# CPU.net
KiCad netlist of a schematic drawn in Altium Designer
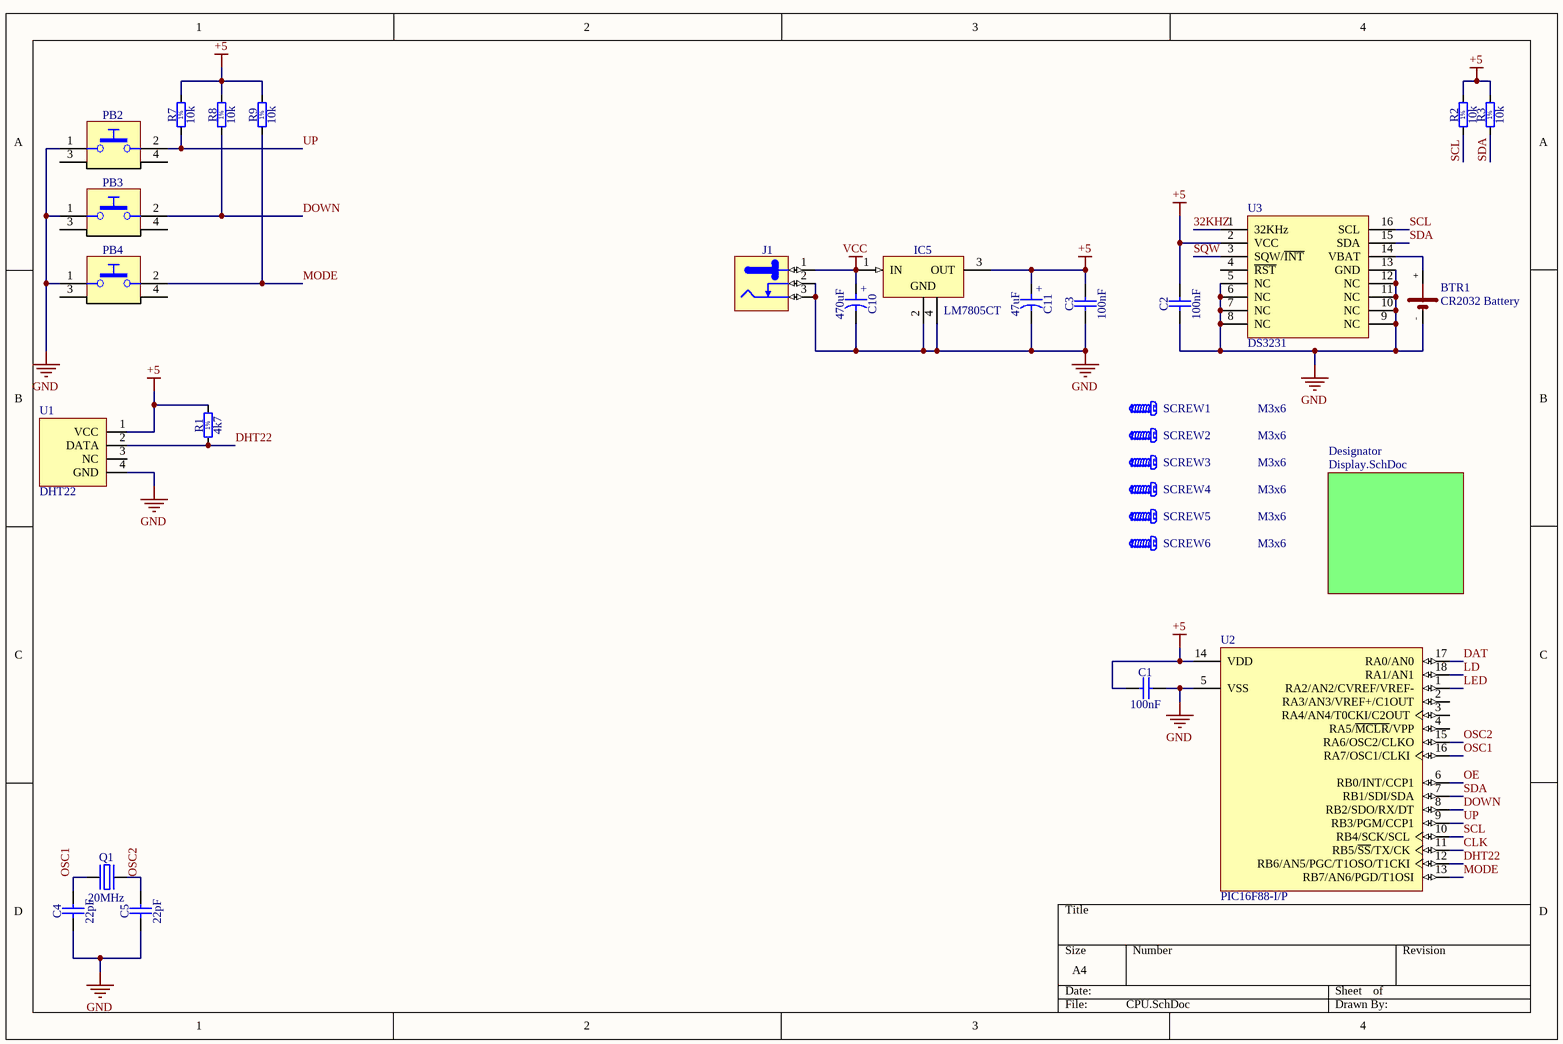
[diagram p0: CPU.SchDoc]

(export (version "E")
  (design (tool "Eeschema 10.0.6"))
  (components
    (comp (ref "BTR1")
      (value "CR2032 Battery")
      (footprint "cr1220")
      (libsource (lib "Shematic") (part "CR2032"))
    )
    (comp (ref "C1")
      (value "100nF")
      (footprint "CAPRR508-350X500X500")
      (description "Non-polarised capacitor")
      (fields
        (field (name "PART NUMBER") "CCR_100NF_50V_10%_X7R_508-350X500X500")
        (field (name "VOLTAGE") "50VDC")
        (field (name "AUTHOR") "CERN DEM JLC")
      )
      (libsource (lib "Capacitors") (part "Capacitor - non polarized"))
    )
    (comp (ref "C2")
      (value "100nF")
      (footprint "CAPRR508-350X500X500")
      (description "Non-polarised capacitor")
      (fields
        (field (name "PART NUMBER") "CCR_100NF_50V_10%_X7R_508-350X500X500")
        (field (name "VOLTAGE") "50VDC")
        (field (name "AUTHOR") "CERN DEM JLC")
      )
      (libsource (lib "Capacitors") (part "Capacitor - non polarized"))
    )
    (comp (ref "C3")
      (value "100nF")
      (footprint "CAPRR508-350X500X500")
      (description "Non-polarised capacitor")
      (fields
        (field (name "PART NUMBER") "CCR_100NF_50V_10%_X7R_508-350X500X500")
        (field (name "VOLTAGE") "50VDC")
        (field (name "AUTHOR") "CERN DEM JLC")
      )
      (libsource (lib "Capacitors") (part "Capacitor - non polarized"))
    )
    (comp (ref "C4")
      (value "22pF")
      (footprint "CAPRR254-254X381X381")
      (description "Non-polarised capacitor")
      (fields
        (field (name "PART NUMBER") "CCR_22PF_100V_5%_C0G_254-254X381X381")
        (field (name "VOLTAGE") "100V")
        (field (name "AUTHOR") "CERN DEM JLC")
      )
      (libsource (lib "Capacitors") (part "Capacitor - non polarized"))
    )
    (comp (ref "C5")
      (value "22pF")
      (footprint "CAPRR254-254X381X381")
      (description "Non-polarised capacitor")
      (fields
        (field (name "PART NUMBER") "CCR_22PF_100V_5%_C0G_254-254X381X381")
        (field (name "VOLTAGE") "100V")
        (field (name "AUTHOR") "CERN DEM JLC")
      )
      (libsource (lib "Capacitors") (part "Capacitor - non polarized"))
    )
    (comp (ref "C10")
      (value "470uF")
      (footprint "CAPPR350-850X1300")
      (description "Polarised capacitor")
      (fields
        (field (name "PART NUMBER") "CAER_470UF_16V_20%_LESR0R056_PANASONIC_FR-A")
        (field (name "VOLTAGE") "16V")
        (field (name "AUTHOR") "CERN DEM JLC")
      )
      (libsource (lib "Capacitors") (part "Capacitor - polarized"))
    )
    (comp (ref "C11")
      (value "47uF")
      (footprint "CAPPR250-500X1100")
      (description "Polarised capacitor")
      (fields
        (field (name "PART NUMBER") "CAER_47UF_25V_20%_250-500X1100")
        (field (name "VOLTAGE") "25V")
        (field (name "AUTHOR") "CERN DEM JLC")
      )
      (libsource (lib "Capacitors") (part "Capacitor - polarized"))
    )
    (comp (ref "IC5")
      (value "LM7805CT")
      (footprint "TO-220-H")
      (description "3-Terminal Regulator 1=IN 2=GND 3=OUT 4=GND")
      (fields
        (field (name "PART NUMBER") "LM7805CT_h")
        (field (name "MANUFACTURER") "FAIRCHILD SEMICONDUCTOR")
        (field (name "AUTHOR") "CERN DEM JLC")
      )
      (libsource (lib "ICs And Semiconductors") (part "REG3+1 1IN-2GND-3OUT+4GND"))
    )
    (comp (ref "J1")
      (value "Jack")
      (footprint "CLIFF_FC68148(DC-10A)")
      (description "12V /  5A, 2.1mm Diameter Pin, DC Power Socket With  Switch. DC10A Type")
      (fields
        (field (name "PART NUMBER") "CLIFF_FC68148(DC-10A)")
        (field (name "MANUFACTURER") "CLIFF ELECTRONIC COMPONENTS")
        (field (name "AUTHOR") "CERN DEM JLC")
      )
      (libsource (lib "Connectors") (part "CLIFF_FC68148(DC-10A)"))
    )
    (comp (ref "PB2")
      (value "Push Button")
      (footprint "PB_TYCO_1-1825027-1")
      (description "Push-Button Switch SPDT")
      (fields
        (field (name "PART NUMBER") "PB_TYCO_1-1825027-1")
        (field (name "MANUFACTURER") "TYCO ELECTRONICS")
        (field (name "AUTHOR") "CERN DEM JLC")
      )
      (libsource (lib "Eletro-mechanical") (part "PB SPST 1NO-2NO 34CASE"))
    )
    (comp (ref "PB3")
      (value "Push Button")
      (footprint "PB_TYCO_1-1825027-1")
      (description "Push-Button Switch SPDT")
      (fields
        (field (name "PART NUMBER") "PB_TYCO_1-1825027-1")
        (field (name "MANUFACTURER") "TYCO ELECTRONICS")
        (field (name "AUTHOR") "CERN DEM JLC")
      )
      (libsource (lib "Eletro-mechanical") (part "PB SPST 1NO-2NO 34CASE"))
    )
    (comp (ref "PB4")
      (value "Push Button")
      (footprint "PB_TYCO_1-1825027-1")
      (description "Push-Button Switch SPDT")
      (fields
        (field (name "PART NUMBER") "PB_TYCO_1-1825027-1")
        (field (name "MANUFACTURER") "TYCO ELECTRONICS")
        (field (name "AUTHOR") "CERN DEM JLC")
      )
      (libsource (lib "Eletro-mechanical") (part "PB SPST 1NO-2NO 34CASE"))
    )
    (comp (ref "Q1")
      (value "20MHz")
      (footprint "XTAL_HC-49/U")
      (description "Quartz Crystal")
      (fields
        (field (name "PART NUMBER") "XTAL_20MHZ_AEL_HC-49/U")
        (field (name "MANUFACTURER") "AEL CRYSTALS")
        (field (name "AUTHOR") "CERN DEM JMW")
      )
      (libsource (lib "ICs And Semiconductors") (part "Quartz Crystal"))
    )
    (comp (ref "R1")
      (value "4k7")
      (footprint "RES1016-630X250")
      (description "Resistor - 1%")
      (fields
        (field (name "PART NUMBER") "RMF_4K7_1%_0.6W_50PPM_1016-630X250")
        (field (name "POWER") "0.6W")
        (field (name "AUTHOR") "CERN DEM JLC")
      )
      (libsource (lib "Resistors") (part "Resistor - 1%"))
    )
    (comp (ref "R2")
      (value "10k")
      (footprint "RES1016-630X250")
      (description "Resistor - 1%")
      (fields
        (field (name "PART NUMBER") "RMF_10K_1%_0.6W_50PPM_1016-630X250")
        (field (name "POWER") "0.6W")
        (field (name "AUTHOR") "CERN DEM JLC")
      )
      (libsource (lib "Resistors") (part "Resistor - 1%"))
    )
    (comp (ref "R3")
      (value "10k")
      (footprint "RES1016-630X250")
      (description "Resistor - 1%")
      (fields
        (field (name "PART NUMBER") "RMF_10K_1%_0.6W_50PPM_1016-630X250")
        (field (name "POWER") "0.6W")
        (field (name "AUTHOR") "CERN DEM JLC")
      )
      (libsource (lib "Resistors") (part "Resistor - 1%"))
    )
    (comp (ref "R7")
      (value "10k")
      (footprint "RES1016-630X250")
      (description "Resistor - 1%")
      (fields
        (field (name "PART NUMBER") "RMF_10K_1%_0.6W_50PPM_1016-630X250")
        (field (name "POWER") "0.6W")
        (field (name "AUTHOR") "CERN DEM JLC")
      )
      (libsource (lib "Resistors") (part "Resistor - 1%"))
    )
    (comp (ref "R8")
      (value "10k")
      (footprint "RES1016-630X250")
      (description "Resistor - 1%")
      (fields
        (field (name "PART NUMBER") "RMF_10K_1%_0.6W_50PPM_1016-630X250")
        (field (name "POWER") "0.6W")
        (field (name "AUTHOR") "CERN DEM JLC")
      )
      (libsource (lib "Resistors") (part "Resistor - 1%"))
    )
    (comp (ref "R9")
      (value "10k")
      (footprint "RES1016-630X250")
      (description "Resistor - 1%")
      (fields
        (field (name "PART NUMBER") "RMF_10K_1%_0.6W_50PPM_1016-630X250")
        (field (name "POWER") "0.6W")
        (field (name "AUTHOR") "CERN DEM JLC")
      )
      (libsource (lib "Resistors") (part "Resistor - 1%"))
    )
    (comp (ref "SCREW1")
      (value "M3x6")
      (footprint "BOSSARD_BN5687-3061605_v")
      (description "Screw")
      (fields
        (field (name "PART NUMBER") "BOSSARD_BN5687-3061605_v")
        (field (name "MANUFACTURER") "BOSSARD")
        (field (name "AUTHOR") "CERN DEM JLC")
      )
      (libsource (lib "Eletro-mechanical") (part "Screw"))
    )
    (comp (ref "SCREW2")
      (value "M3x6")
      (footprint "BOSSARD_BN5687-3061605_v")
      (description "Screw")
      (fields
        (field (name "PART NUMBER") "BOSSARD_BN5687-3061605_v")
        (field (name "MANUFACTURER") "BOSSARD")
        (field (name "AUTHOR") "CERN DEM JLC")
      )
      (libsource (lib "Eletro-mechanical") (part "Screw"))
    )
    (comp (ref "SCREW3")
      (value "M3x6")
      (footprint "BOSSARD_BN5687-3061605_v")
      (description "Screw")
      (fields
        (field (name "PART NUMBER") "BOSSARD_BN5687-3061605_v")
        (field (name "MANUFACTURER") "BOSSARD")
        (field (name "AUTHOR") "CERN DEM JLC")
      )
      (libsource (lib "Eletro-mechanical") (part "Screw"))
    )
    (comp (ref "SCREW4")
      (value "M3x6")
      (footprint "BOSSARD_BN5687-3061605_v")
      (description "Screw")
      (fields
        (field (name "PART NUMBER") "BOSSARD_BN5687-3061605_v")
        (field (name "MANUFACTURER") "BOSSARD")
        (field (name "AUTHOR") "CERN DEM JLC")
      )
      (libsource (lib "Eletro-mechanical") (part "Screw"))
    )
    (comp (ref "SCREW5")
      (value "M3x6")
      (footprint "BOSSARD_BN5687-3061605_v")
      (description "Screw")
      (fields
        (field (name "PART NUMBER") "BOSSARD_BN5687-3061605_v")
        (field (name "MANUFACTURER") "BOSSARD")
        (field (name "AUTHOR") "CERN DEM JLC")
      )
      (libsource (lib "Eletro-mechanical") (part "Screw"))
    )
    (comp (ref "SCREW6")
      (value "M3x6")
      (footprint "BOSSARD_BN5687-3061605_v")
      (description "Screw")
      (fields
        (field (name "PART NUMBER") "BOSSARD_BN5687-3061605_v")
        (field (name "MANUFACTURER") "BOSSARD")
        (field (name "AUTHOR") "CERN DEM JLC")
      )
      (libsource (lib "Eletro-mechanical") (part "Screw"))
    )
    (comp (ref "U1") (value "DHT22") (footprint "DHT22_HOR") (libsource (lib "Shematic") (part "DHT22")))
    (comp (ref "U2")
      (value "PIC16F88-I/P")
      (footprint "PDIP300-P18")
      (fields (field (name "PUBLISHER") "Altium Limited"))
      (libsource (lib "Microchip Microcontroller 8-Bit PIC16") (part "PIC16F88-I/P"))
    )
    (comp (ref "U3")
      (value "DS3231")
      (footprint "SOIC16W")
      (libsource (lib "Tansa_Server_Schematic_Library") (part "DS3231"))
    )
  )
  (nets
    (net (code "1") (name "+5") (class "Default")
      (node (ref "C1") (pin "1") (pinfunction "1_1") (pintype "passive"))
      (node (ref "C11") (pin "1") (pinfunction "1_1") (pintype "passive"))
      (node (ref "C2") (pin "2") (pinfunction "2_2") (pintype "passive"))
      (node (ref "C3") (pin "2") (pinfunction "2_2") (pintype "passive"))
      (node (ref "IC5") (pin "3") (pinfunction "OUT_3") (pintype "power_in"))
      (node (ref "R1") (pin "2") (pinfunction "2_2") (pintype "passive"))
      (node (ref "R2") (pin "2") (pinfunction "2_2") (pintype "passive"))
      (node (ref "R3") (pin "2") (pinfunction "2_2") (pintype "passive"))
      (node (ref "R7") (pin "2") (pinfunction "2_2") (pintype "passive"))
      (node (ref "R8") (pin "2") (pinfunction "2_2") (pintype "passive"))
      (node (ref "R9") (pin "2") (pinfunction "2_2") (pintype "passive"))
      (node (ref "U1") (pin "1") (pinfunction "VCC_1") (pintype "passive"))
      (node (ref "U2") (pin "14") (pinfunction "VDD_14") (pintype "power_in"))
      (node (ref "U3") (pin "2") (pinfunction "VCC_2") (pintype "passive"))
    )
    (net (code "2") (name "/32KHZ") (class "Default")
      (node (ref "U3") (pin "1") (pinfunction "32KHz_1") (pintype "passive"))
    )
    (net (code "3") (name "/CLK") (class "Default")
      (node (ref "U2") (pin "11") (pinfunction "RB5/~{SS}/TX/CK_11") (pintype "bidirectional"))
    )
    (net (code "4") (name "/DAT") (class "Default")
      (node (ref "U2") (pin "17") (pinfunction "RA0/AN0_17") (pintype "bidirectional"))
    )
    (net (code "5") (name "/DHT22") (class "Default")
      (node (ref "R1") (pin "1") (pinfunction "1_1") (pintype "passive"))
      (node (ref "U1") (pin "2") (pinfunction "DATA_2") (pintype "passive"))
      (node (ref "U2") (pin "12") (pinfunction "RB6/AN5/PGC/T1OSO/T1CKI_12") (pintype "bidirectional"))
    )
    (net (code "6") (name "/DOWN") (class "Default")
      (node (ref "PB3") (pin "2") (pinfunction "2_2") (pintype "passive"))
      (node (ref "R8") (pin "1") (pinfunction "1_1") (pintype "passive"))
      (node (ref "U2") (pin "8") (pinfunction "RB2/SDO/RX/DT_8") (pintype "bidirectional"))
    )
    (net (code "7") (name "/LD") (class "Default")
      (node (ref "U2") (pin "18") (pinfunction "RA1/AN1_18") (pintype "bidirectional"))
    )
    (net (code "8") (name "/LED") (class "Default")
      (node (ref "U2") (pin "1") (pinfunction "RA2/AN2/CVREF/VREF-_1") (pintype "bidirectional"))
    )
    (net (code "9") (name "/MODE") (class "Default")
      (node (ref "PB4") (pin "2") (pinfunction "2_2") (pintype "passive"))
      (node (ref "R9") (pin "1") (pinfunction "1_1") (pintype "passive"))
      (node (ref "U2") (pin "13") (pinfunction "RB7/AN6/PGD/T1OSI_13") (pintype "bidirectional"))
    )
    (net (code "10") (name "/OE") (class "Default")
      (node (ref "U2") (pin "6") (pinfunction "RB0/INT/CCP1_6") (pintype "bidirectional"))
    )
    (net (code "11") (name "/OSC1") (class "Default")
      (node (ref "C4") (pin "2") (pinfunction "2_2") (pintype "passive"))
      (node (ref "Q1") (pin "1") (pinfunction "OSC1_1") (pintype "passive"))
      (node (ref "U2") (pin "16") (pinfunction "RA7/OSC1/CLKI_16") (pintype "bidirectional"))
    )
    (net (code "12") (name "/OSC2") (class "Default")
      (node (ref "C5") (pin "2") (pinfunction "2_2") (pintype "passive"))
      (node (ref "Q1") (pin "2") (pinfunction "OSC2_2") (pintype "passive"))
      (node (ref "U2") (pin "15") (pinfunction "RA6/OSC2/CLKO_15") (pintype "bidirectional"))
    )
    (net (code "13") (name "/SCL") (class "Default")
      (node (ref "R2") (pin "1") (pinfunction "1_1") (pintype "passive"))
      (node (ref "U2") (pin "10") (pinfunction "RB4/SCK/SCL_10") (pintype "bidirectional"))
      (node (ref "U3") (pin "16") (pinfunction "SCL_16") (pintype "passive"))
    )
    (net (code "14") (name "/SDA") (class "Default")
      (node (ref "R3") (pin "1") (pinfunction "1_1") (pintype "passive"))
      (node (ref "U2") (pin "7") (pinfunction "RB1/SDI/SDA_7") (pintype "bidirectional"))
      (node (ref "U3") (pin "15") (pinfunction "SDA_15") (pintype "passive"))
    )
    (net (code "15") (name "/SQW") (class "Default")
      (node (ref "U3") (pin "3") (pinfunction "SQW/~{INT}_3") (pintype "power_in"))
    )
    (net (code "16") (name "/UP") (class "Default")
      (node (ref "PB2") (pin "2") (pinfunction "2_2") (pintype "passive"))
      (node (ref "R7") (pin "1") (pinfunction "1_1") (pintype "passive"))
      (node (ref "U2") (pin "9") (pinfunction "RB3/PGM/CCP1_9") (pintype "bidirectional"))
    )
    (net (code "17") (name "GND") (class "Default")
      (node (ref "BTR1") (pin "-") (pinfunction "-_-") (pintype "passive"))
      (node (ref "C1") (pin "2") (pinfunction "2_2") (pintype "passive"))
      (node (ref "C10") (pin "2") (pinfunction "2_2") (pintype "passive"))
      (node (ref "C11") (pin "2") (pinfunction "2_2") (pintype "passive"))
      (node (ref "C2") (pin "1") (pinfunction "1_1") (pintype "passive"))
      (node (ref "C3") (pin "1") (pinfunction "1_1") (pintype "passive"))
      (node (ref "C4") (pin "1") (pinfunction "1_1") (pintype "passive"))
      (node (ref "C5") (pin "1") (pinfunction "1_1") (pintype "passive"))
      (node (ref "IC5") (pin "2") (pinfunction "GND_2") (pintype "power_in"))
      (node (ref "IC5") (pin "4") (pinfunction "GND_4") (pintype "power_in"))
      (node (ref "J1") (pin "2") (pinfunction "2_2") (pintype "bidirectional"))
      (node (ref "J1") (pin "3") (pinfunction "3_3") (pintype "bidirectional"))
      (node (ref "PB2") (pin "1") (pinfunction "1_1") (pintype "passive"))
      (node (ref "PB3") (pin "1") (pinfunction "1_1") (pintype "passive"))
      (node (ref "PB4") (pin "1") (pinfunction "1_1") (pintype "passive"))
      (node (ref "U1") (pin "4") (pinfunction "GND_4") (pintype "passive"))
      (node (ref "U2") (pin "5") (pinfunction "VSS_5") (pintype "power_in"))
      (node (ref "U3") (pin "10") (pinfunction "NC_10") (pintype "passive"))
      (node (ref "U3") (pin "11") (pinfunction "NC_11") (pintype "passive"))
      (node (ref "U3") (pin "12") (pinfunction "NC_12") (pintype "passive"))
      (node (ref "U3") (pin "13") (pinfunction "GND_13") (pintype "passive"))
      (node (ref "U3") (pin "5") (pinfunction "NC_5") (pintype "open_emitter"))
      (node (ref "U3") (pin "6") (pinfunction "NC_6") (pintype "passive"))
      (node (ref "U3") (pin "7") (pinfunction "NC_7") (pintype "passive"))
      (node (ref "U3") (pin "8") (pinfunction "NC_8") (pintype "passive"))
      (node (ref "U3") (pin "9") (pinfunction "NC_9") (pintype "passive"))
    )
    (net (code "18") (name "Net-(U3-VBAT)") (class "Default")
      (node (ref "BTR1") (pin "+") (pinfunction "+_+") (pintype "passive"))
      (node (ref "U3") (pin "14") (pinfunction "VBAT_14") (pintype "passive"))
    )
    (net (code "19") (name "VCC") (class "Default")
      (node (ref "C10") (pin "1") (pinfunction "1_1") (pintype "passive"))
      (node (ref "IC5") (pin "1") (pinfunction "IN_1") (pintype "input"))
      (node (ref "J1") (pin "1") (pinfunction "1_1") (pintype "bidirectional"))
    )
    (net (code "20") (name "unconnected-(PB2-Pad3)") (class "Default")
      (node (ref "PB2") (pin "3") (pinfunction "3_3") (pintype "passive"))
    )
    (net (code "21") (name "unconnected-(PB2-Pad4)") (class "Default")
      (node (ref "PB2") (pin "4") (pinfunction "4_4") (pintype "passive"))
    )
    (net (code "22") (name "unconnected-(PB3-Pad3)") (class "Default")
      (node (ref "PB3") (pin "3") (pinfunction "3_3") (pintype "passive"))
    )
    (net (code "23") (name "unconnected-(PB3-Pad4)") (class "Default")
      (node (ref "PB3") (pin "4") (pinfunction "4_4") (pintype "passive"))
    )
    (net (code "24") (name "unconnected-(PB4-Pad3)") (class "Default")
      (node (ref "PB4") (pin "3") (pinfunction "3_3") (pintype "passive"))
    )
    (net (code "25") (name "unconnected-(PB4-Pad4)") (class "Default")
      (node (ref "PB4") (pin "4") (pinfunction "4_4") (pintype "passive"))
    )
    (net (code "26") (name "unconnected-(U1-NC-Pad3)") (class "Default")
      (node (ref "U1") (pin "3") (pinfunction "NC_3") (pintype "passive"))
    )
    (net (code "27") (name "unconnected-(U2-RA3{slash}AN3{slash}VREF+{slash}C1OUT-Pad2)") (class "Default")
      (node (ref "U2") (pin "2") (pinfunction "RA3/AN3/VREF+/C1OUT_2") (pintype "bidirectional"))
    )
    (net (code "28") (name "unconnected-(U2-RA4{slash}AN4{slash}T0CKI{slash}C2OUT-Pad3)") (class "Default")
      (node (ref "U2") (pin "3") (pinfunction "RA4/AN4/T0CKI/C2OUT_3") (pintype "bidirectional"))
    )
    (net (code "29") (name "unconnected-(U2-RA5{slash}~{MCLR}{slash}VPP-Pad4)") (class "Default")
      (node (ref "U2") (pin "4") (pinfunction "RA5/~{MCLR}/VPP_4") (pintype "bidirectional"))
    )
    (net (code "30") (name "unconnected-(U3-~{RST}-Pad4)") (class "Default")
      (node (ref "U3") (pin "4") (pinfunction "~{RST}_4") (pintype "power_in"))
    )
  )
)
